# can-stm32g4.net
KiCad netlist of a schematic drawn in Altium Designer
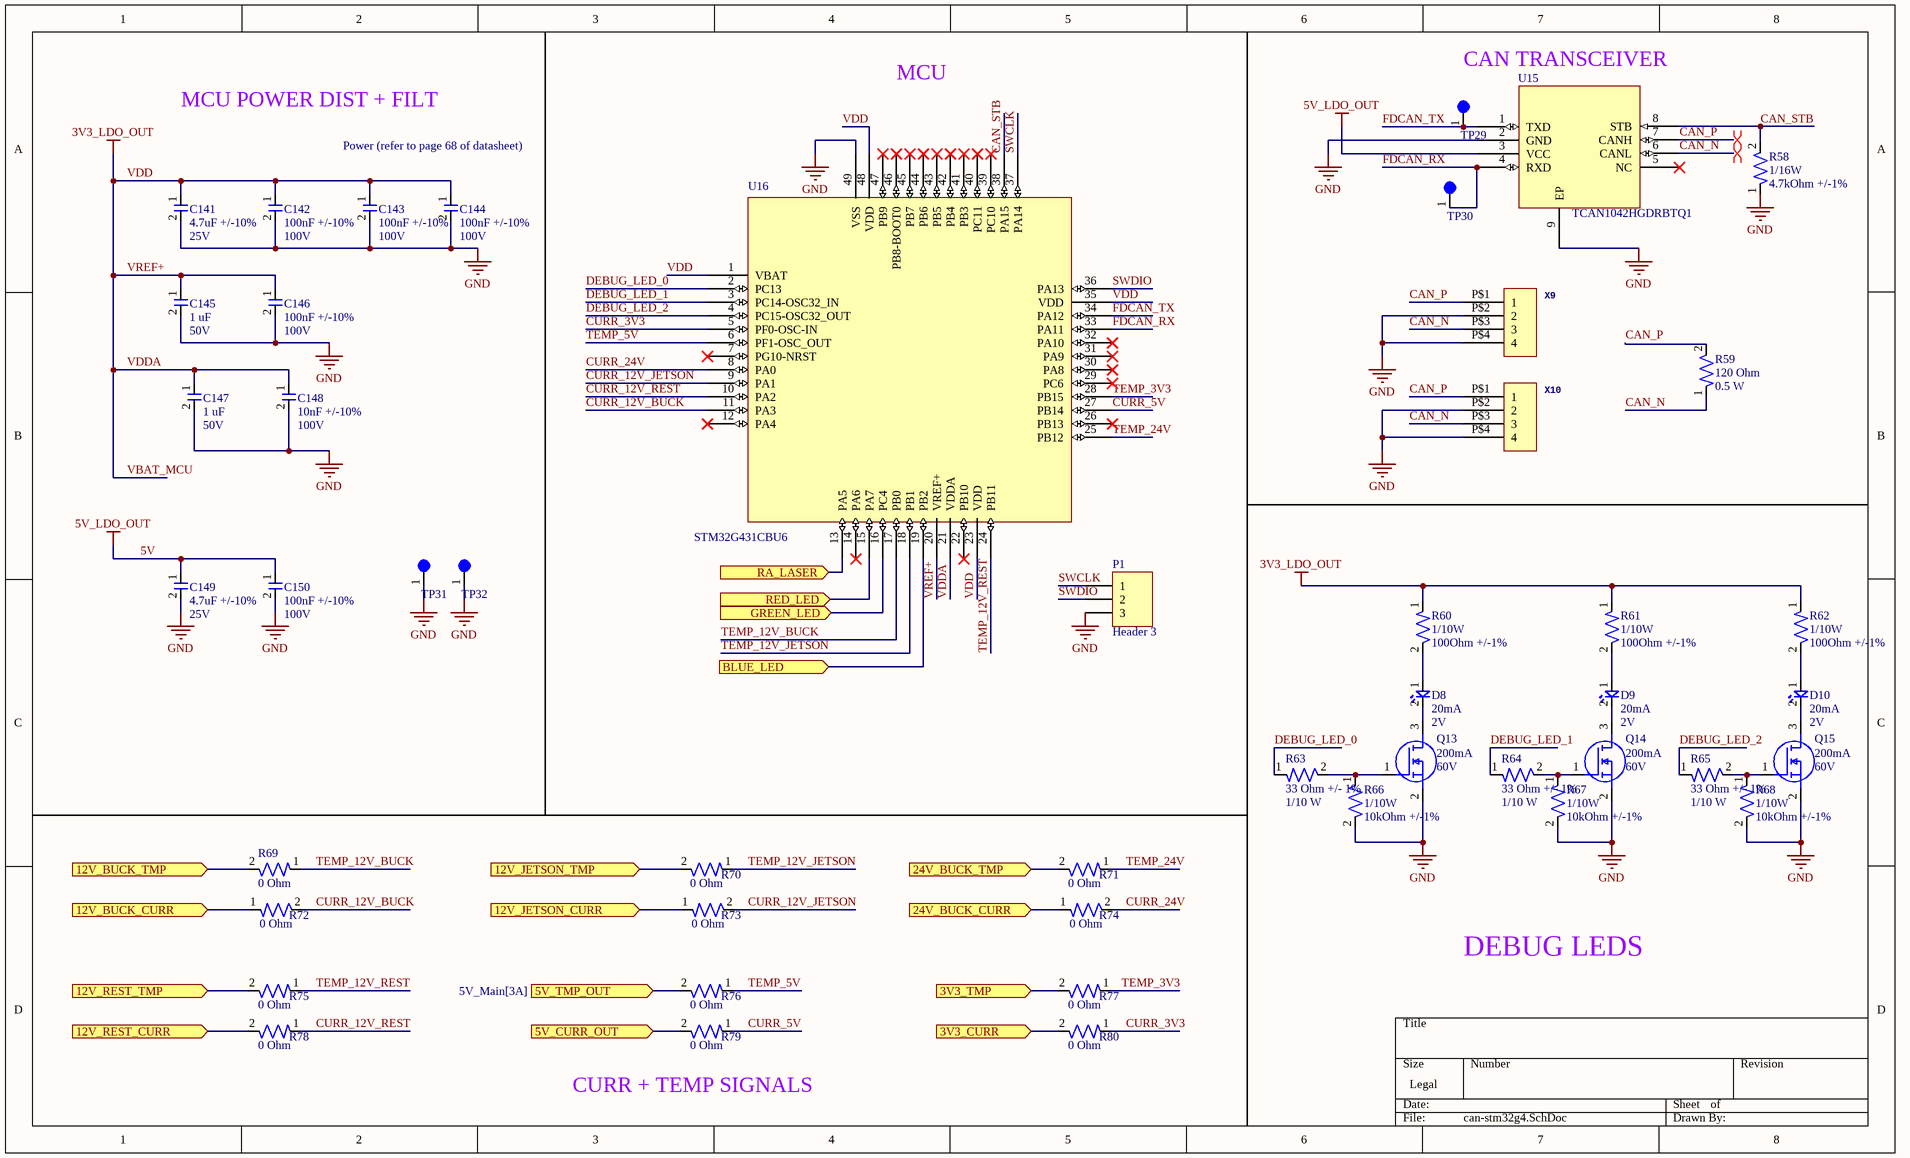
[diagram p0: can-stm32g4.SchDoc]

(export (version "E")
  (design (tool "Eeschema 10.0.6"))
  (components
    (comp (ref "C141")
      (value "TMK107BBJ475KA-T")
      (footprint "CAP-0603")
      (description "4.7 µF ±10% 25V Ceramic Capacitor X5R 0603 (1608 Metric)")
      (fields
        (field (name "MANUFACTURER") "Taiyo Yuden")
        (field (name "CAPACITANCE") "4.7uF +/-10%")
        (field (name "VOLTAGE RATING") "25V")
      )
      (libsource (lib "MasterLib") (part "CAP-4.7U-0001"))
    )
    (comp (ref "C142")
      (value "CC0603KRX7R0BB104")
      (footprint "CAP-0603")
      (description "CAP CER 0.1UF 100V X7R 0603")
      (fields
        (field (name "MANUFACTURER") "YAGEO")
        (field (name "CAPACITANCE") "100nF +/-10%")
        (field (name "VOLTAGE RATING") "100V")
      )
      (libsource (lib "MasterLib") (part "CAP-100N-0001"))
    )
    (comp (ref "C143")
      (value "CC0603KRX7R0BB104")
      (footprint "CAP-0603")
      (description "CAP CER 0.1UF 100V X7R 0603")
      (fields
        (field (name "MANUFACTURER") "YAGEO")
        (field (name "CAPACITANCE") "100nF +/-10%")
        (field (name "VOLTAGE RATING") "100V")
      )
      (libsource (lib "MasterLib") (part "CAP-100N-0001"))
    )
    (comp (ref "C144")
      (value "CC0603KRX7R0BB104")
      (footprint "CAP-0603")
      (description "CAP CER 0.1UF 100V X7R 0603")
      (fields
        (field (name "MANUFACTURER") "YAGEO")
        (field (name "CAPACITANCE") "100nF +/-10%")
        (field (name "VOLTAGE RATING") "100V")
      )
      (libsource (lib "MasterLib") (part "CAP-100N-0001"))
    )
    (comp (ref "C145")
      (value "UMK107AB7105KA-T")
      (footprint "CAP-0603")
      (description "1 µF ±10% 50V Ceramic Capacitor X7R 0603 (1608 Metric)")
      (fields (field (name "CAPACITANCE") "1 uF") (field (name "VOLTAGE") "50V"))
      (libsource (lib "MasterLib") (part "CAP-1U-0002"))
    )
    (comp (ref "C146")
      (value "CC0603KRX7R0BB104")
      (footprint "CAP-0603")
      (description "CAP CER 0.1UF 100V X7R 0603")
      (fields
        (field (name "MANUFACTURER") "YAGEO")
        (field (name "CAPACITANCE") "100nF +/-10%")
        (field (name "VOLTAGE RATING") "100V")
      )
      (libsource (lib "MasterLib") (part "CAP-100N-0001"))
    )
    (comp (ref "C147")
      (value "UMK107AB7105KA-T")
      (footprint "CAP-0603")
      (description "1 µF ±10% 50V Ceramic Capacitor X7R 0603 (1608 Metric)")
      (fields (field (name "CAPACITANCE") "1 uF") (field (name "VOLTAGE") "50V"))
      (libsource (lib "MasterLib") (part "CAP-1U-0002"))
    )
    (comp (ref "C148")
      (value "CC0402KRX7R0BB103")
      (footprint "CAP-0402")
      (description "10000 pF ±10% 100V Ceramic Capacitor X7R 0402 (1005 Metric)")
      (fields
        (field (name "MANUFACTURER") "YAGEO")
        (field (name "CAPACITANCE") "10nF +/-10%")
        (field (name "VOLTAGE RATING") "100V")
      )
      (libsource (lib "MasterLib") (part "CAP-10N-0001"))
    )
    (comp (ref "C149")
      (value "TMK107BBJ475KA-T")
      (footprint "CAP-0603")
      (description "4.7 µF ±10% 25V Ceramic Capacitor X5R 0603 (1608 Metric)")
      (fields
        (field (name "MANUFACTURER") "Taiyo Yuden")
        (field (name "CAPACITANCE") "4.7uF +/-10%")
        (field (name "VOLTAGE RATING") "25V")
      )
      (libsource (lib "MasterLib") (part "CAP-4.7U-0001"))
    )
    (comp (ref "C150")
      (value "CC0603KRX7R0BB104")
      (footprint "CAP-0603")
      (description "CAP CER 0.1UF 100V X7R 0603")
      (fields
        (field (name "MANUFACTURER") "YAGEO")
        (field (name "CAPACITANCE") "100nF +/-10%")
        (field (name "VOLTAGE RATING") "100V")
      )
      (libsource (lib "MasterLib") (part "CAP-100N-0001"))
    )
    (comp (ref "D8")
      (value "150060AS75000")
      (footprint "LED-0603")
      (description "CAP CER 0.1UF 100V X7R 0603")
      (fields
        (field (name "MANUFACTURER") "Wurth Electronik")
        (field (name "CURRENT RATING") "20mA")
        (field (name "VF") "2V")
      )
      (libsource (lib "MasterLib") (part "LED_Amber_0001"))
    )
    (comp (ref "D9")
      (value "150060AS75000")
      (footprint "LED-0603")
      (description "CAP CER 0.1UF 100V X7R 0603")
      (fields
        (field (name "MANUFACTURER") "Wurth Electronik")
        (field (name "CURRENT RATING") "20mA")
        (field (name "VF") "2V")
      )
      (libsource (lib "MasterLib") (part "LED_Amber_0001"))
    )
    (comp (ref "D10")
      (value "150060AS75000")
      (footprint "LED-0603")
      (description "CAP CER 0.1UF 100V X7R 0603")
      (fields
        (field (name "MANUFACTURER") "Wurth Electronik")
        (field (name "CURRENT RATING") "20mA")
        (field (name "VF") "2V")
      )
      (libsource (lib "MasterLib") (part "LED_Amber_0001"))
    )
    (comp (ref "P1")
      (value "Header 3")
      (footprint "HDR1X3")
      (description "Header, 3-Pin")
      (fields (field (name "PUBLISHER") "Altium Limited"))
      (libsource (lib "Miscellaneous Connectors") (part "Header 3"))
    )
    (comp (ref "Q13")
      (value "T2N7002AK,LM")
      (footprint "NMOS-SOT23-3")
      (description "MOSFET N-CH 60V 200MA SOT23")
      (fields
        (field (name "MANUFACTURER") "Toshiba")
        (field (name "ID-CONTINUOUS") "200mA")
        (field (name "VDS-MAX") "60V")
      )
      (libsource (lib "MasterLib") (part "NMOS-200MA-0001"))
    )
    (comp (ref "Q14")
      (value "T2N7002AK,LM")
      (footprint "NMOS-SOT23-3")
      (description "MOSFET N-CH 60V 200MA SOT23")
      (fields
        (field (name "MANUFACTURER") "Toshiba")
        (field (name "ID-CONTINUOUS") "200mA")
        (field (name "VDS-MAX") "60V")
      )
      (libsource (lib "MasterLib") (part "NMOS-200MA-0001"))
    )
    (comp (ref "Q15")
      (value "T2N7002AK,LM")
      (footprint "NMOS-SOT23-3")
      (description "MOSFET N-CH 60V 200MA SOT23")
      (fields
        (field (name "MANUFACTURER") "Toshiba")
        (field (name "ID-CONTINUOUS") "200mA")
        (field (name "VDS-MAX") "60V")
      )
      (libsource (lib "MasterLib") (part "NMOS-200MA-0001"))
    )
    (comp (ref "R58")
      (value "RC0402FR-074K7P")
      (footprint "RES-0402")
      (description "RES SMD 4.7K OHM 1% 1/16W 0402")
      (fields
        (field (name "MANUFACTURER") "YAGEO")
        (field (name "POWER RATING") "1/16W")
        (field (name "RESISTANCE") "4.7kOhm +/-1%")
      )
      (libsource (lib "MasterLib") (part "RES-4.7K-0001"))
    )
    (comp (ref "R59")
      (value "CRGH1206F120R")
      (footprint "RES-1206")
      (description "120 Ohms ±1% 0.5W, 1/2W Chip Resistor 1206 (3216 Metric) Thick Film")
      (fields
        (field (name "TOLERANCE") "1%")
        (field (name "RESISTANCE") "120 Ohm")
        (field (name "POWER") "0.5 W")
      )
      (libsource (lib "MasterLib") (part "RES-120-0002"))
    )
    (comp (ref "R60")
      (value "AC0603FR-10100RL")
      (footprint "RES-0603")
      (description "100 Ohms ±1% 0.1W, 1/10W Chip Resistor 0603 (1608 Metric) Automotive AEC-Q200 Thick Film")
      (fields
        (field (name "MANUFACTURER") "YAGEO")
        (field (name "POWER RATING") "1/10W")
        (field (name "RESISTANCE") "100Ohm +/-1%")
      )
      (libsource (lib "MasterLib") (part "RES-100-0002"))
    )
    (comp (ref "R61")
      (value "AC0603FR-10100RL")
      (footprint "RES-0603")
      (description "100 Ohms ±1% 0.1W, 1/10W Chip Resistor 0603 (1608 Metric) Automotive AEC-Q200 Thick Film")
      (fields
        (field (name "MANUFACTURER") "YAGEO")
        (field (name "POWER RATING") "1/10W")
        (field (name "RESISTANCE") "100Ohm +/-1%")
      )
      (libsource (lib "MasterLib") (part "RES-100-0002"))
    )
    (comp (ref "R62")
      (value "AC0603FR-10100RL")
      (footprint "RES-0603")
      (description "100 Ohms ±1% 0.1W, 1/10W Chip Resistor 0603 (1608 Metric) Automotive AEC-Q200 Thick Film")
      (fields
        (field (name "MANUFACTURER") "YAGEO")
        (field (name "POWER RATING") "1/10W")
        (field (name "RESISTANCE") "100Ohm +/-1%")
      )
      (libsource (lib "MasterLib") (part "RES-100-0002"))
    )
    (comp (ref "R63")
      (value "ERJ2RKF33R0X")
      (footprint "RES-0402")
      (description "100mW Thick Film Resistors ±100ppm/℃ ±1% -55℃~+155℃ 33Ω 0402  Chip Resistor - Surface Mount ROHS")
      (fields
        (field (name "RESISTANCE") "33 Ohm +/- 1%")
        (field (name "POWER") "1/10 W")
        (field (name "JLC PART NUMBER") "C278594")
      )
      (libsource (lib "MasterLib") (part "RES-33-0003-JLC"))
    )
    (comp (ref "R64")
      (value "ERJ2RKF33R0X")
      (footprint "RES-0402")
      (description "100mW Thick Film Resistors ±100ppm/℃ ±1% -55℃~+155℃ 33Ω 0402  Chip Resistor - Surface Mount ROHS")
      (fields
        (field (name "RESISTANCE") "33 Ohm +/- 1%")
        (field (name "POWER") "1/10 W")
        (field (name "JLC PART NUMBER") "C278594")
      )
      (libsource (lib "MasterLib") (part "RES-33-0003-JLC"))
    )
    (comp (ref "R65")
      (value "ERJ2RKF33R0X")
      (footprint "RES-0402")
      (description "100mW Thick Film Resistors ±100ppm/℃ ±1% -55℃~+155℃ 33Ω 0402  Chip Resistor - Surface Mount ROHS")
      (fields
        (field (name "RESISTANCE") "33 Ohm +/- 1%")
        (field (name "POWER") "1/10 W")
        (field (name "JLC PART NUMBER") "C278594")
      )
      (libsource (lib "MasterLib") (part "RES-33-0003-JLC"))
    )
    (comp (ref "R66")
      (value "RC0603FR-0710KP")
      (footprint "RES-0603")
      (description "RES SMD 10K OHM 1% 1/10W 0603")
      (fields
        (field (name "MANUFACTURER") "YAGEO")
        (field (name "POWER RATING") "1/10W")
        (field (name "RESISTANCE") "10kOhm +/-1%")
      )
      (libsource (lib "MasterLib") (part "RES-10K-0002"))
    )
    (comp (ref "R67")
      (value "RC0603FR-0710KP")
      (footprint "RES-0603")
      (description "RES SMD 10K OHM 1% 1/10W 0603")
      (fields
        (field (name "MANUFACTURER") "YAGEO")
        (field (name "POWER RATING") "1/10W")
        (field (name "RESISTANCE") "10kOhm +/-1%")
      )
      (libsource (lib "MasterLib") (part "RES-10K-0002"))
    )
    (comp (ref "R68")
      (value "RC0603FR-0710KP")
      (footprint "RES-0603")
      (description "RES SMD 10K OHM 1% 1/10W 0603")
      (fields
        (field (name "MANUFACTURER") "YAGEO")
        (field (name "POWER RATING") "1/10W")
        (field (name "RESISTANCE") "10kOhm +/-1%")
      )
      (libsource (lib "MasterLib") (part "RES-10K-0002"))
    )
    (comp (ref "R69")
      (value "RMCF0603ZT0R00")
      (footprint "RES-0603")
      (description "0 Ohms Jumper 0.1W, 1/10W Chip Resistor 0603 (1608 Metric) Automotive AEC-Q200 Thick Film")
      (fields (field (name "RESISTANCE") "0 Ohm"))
      (libsource (lib "MasterLib") (part "RES-0-0001"))
    )
    (comp (ref "R70")
      (value "RMCF0603ZT0R00")
      (footprint "RES-0603")
      (description "0 Ohms Jumper 0.1W, 1/10W Chip Resistor 0603 (1608 Metric) Automotive AEC-Q200 Thick Film")
      (fields (field (name "RESISTANCE") "0 Ohm"))
      (libsource (lib "MasterLib") (part "RES-0-0001"))
    )
    (comp (ref "R71")
      (value "RMCF0603ZT0R00")
      (footprint "RES-0603")
      (description "0 Ohms Jumper 0.1W, 1/10W Chip Resistor 0603 (1608 Metric) Automotive AEC-Q200 Thick Film")
      (fields (field (name "RESISTANCE") "0 Ohm"))
      (libsource (lib "MasterLib") (part "RES-0-0001"))
    )
    (comp (ref "R72")
      (value "RMCF0603ZT0R00")
      (footprint "RES-0603")
      (description "0 Ohms Jumper 0.1W, 1/10W Chip Resistor 0603 (1608 Metric) Automotive AEC-Q200 Thick Film")
      (fields (field (name "RESISTANCE") "0 Ohm"))
      (libsource (lib "MasterLib") (part "RES-0-0001"))
    )
    (comp (ref "R73")
      (value "RMCF0603ZT0R00")
      (footprint "RES-0603")
      (description "0 Ohms Jumper 0.1W, 1/10W Chip Resistor 0603 (1608 Metric) Automotive AEC-Q200 Thick Film")
      (fields (field (name "RESISTANCE") "0 Ohm"))
      (libsource (lib "MasterLib") (part "RES-0-0001"))
    )
    (comp (ref "R74")
      (value "RMCF0603ZT0R00")
      (footprint "RES-0603")
      (description "0 Ohms Jumper 0.1W, 1/10W Chip Resistor 0603 (1608 Metric) Automotive AEC-Q200 Thick Film")
      (fields (field (name "RESISTANCE") "0 Ohm"))
      (libsource (lib "MasterLib") (part "RES-0-0001"))
    )
    (comp (ref "R75")
      (value "RMCF0603ZT0R00")
      (footprint "RES-0603")
      (description "0 Ohms Jumper 0.1W, 1/10W Chip Resistor 0603 (1608 Metric) Automotive AEC-Q200 Thick Film")
      (fields (field (name "RESISTANCE") "0 Ohm"))
      (libsource (lib "MasterLib") (part "RES-0-0001"))
    )
    (comp (ref "R76")
      (value "RMCF0603ZT0R00")
      (footprint "RES-0603")
      (description "0 Ohms Jumper 0.1W, 1/10W Chip Resistor 0603 (1608 Metric) Automotive AEC-Q200 Thick Film")
      (fields (field (name "RESISTANCE") "0 Ohm"))
      (libsource (lib "MasterLib") (part "RES-0-0001"))
    )
    (comp (ref "R77")
      (value "RMCF0603ZT0R00")
      (footprint "RES-0603")
      (description "0 Ohms Jumper 0.1W, 1/10W Chip Resistor 0603 (1608 Metric) Automotive AEC-Q200 Thick Film")
      (fields (field (name "RESISTANCE") "0 Ohm"))
      (libsource (lib "MasterLib") (part "RES-0-0001"))
    )
    (comp (ref "R78")
      (value "RMCF0603ZT0R00")
      (footprint "RES-0603")
      (description "0 Ohms Jumper 0.1W, 1/10W Chip Resistor 0603 (1608 Metric) Automotive AEC-Q200 Thick Film")
      (fields (field (name "RESISTANCE") "0 Ohm"))
      (libsource (lib "MasterLib") (part "RES-0-0001"))
    )
    (comp (ref "R79")
      (value "RMCF0603ZT0R00")
      (footprint "RES-0603")
      (description "0 Ohms Jumper 0.1W, 1/10W Chip Resistor 0603 (1608 Metric) Automotive AEC-Q200 Thick Film")
      (fields (field (name "RESISTANCE") "0 Ohm"))
      (libsource (lib "MasterLib") (part "RES-0-0001"))
    )
    (comp (ref "R80")
      (value "RMCF0603ZT0R00")
      (footprint "RES-0603")
      (description "0 Ohms Jumper 0.1W, 1/10W Chip Resistor 0603 (1608 Metric) Automotive AEC-Q200 Thick Film")
      (fields (field (name "RESISTANCE") "0 Ohm"))
      (libsource (lib "MasterLib") (part "RES-0-0001"))
    )
    (comp (ref "TP29")
      (value "5003")
      (footprint "TEST-POINT-0001")
      (description "Oranange PC Test Point, Miniature Phoisphor Bronze Silver Plating Through Hole Mounting Type")
      (libsource (lib "MasterLib") (part "TEST-POINT-0001"))
    )
    (comp (ref "TP30")
      (value "5003")
      (footprint "TEST-POINT-0001")
      (description "Oranange PC Test Point, Miniature Phoisphor Bronze Silver Plating Through Hole Mounting Type")
      (libsource (lib "MasterLib") (part "TEST-POINT-0001"))
    )
    (comp (ref "TP31")
      (value "5003")
      (footprint "TEST-POINT-0001")
      (description "Oranange PC Test Point, Miniature Phoisphor Bronze Silver Plating Through Hole Mounting Type")
      (libsource (lib "MasterLib") (part "TEST-POINT-0001"))
    )
    (comp (ref "TP32")
      (value "5003")
      (footprint "TEST-POINT-0001")
      (description "Oranange PC Test Point, Miniature Phoisphor Bronze Silver Plating Through Hole Mounting Type")
      (libsource (lib "MasterLib") (part "TEST-POINT-0001"))
    )
    (comp (ref "U15")
      (value "TCAN1042HGDRBTQ1")
      (footprint "IC-8-VSON")
      (description "1/1 Transceiver CANbus 8-VSON (3x3)")
      (fields (field (name "MANUFACTURER") "Texas Instrument"))
      (libsource (lib "MasterLib") (part "IC-CAN-TRANSCEIVER-0002"))
    )
    (comp (ref "U16")
      (value "STM32G431CBU6")
      (footprint "MCU-UFQFPN48")
      (libsource (lib "MasterLib") (part "IC-STM32G431CBU6"))
    )
    (comp (ref "X9")
      (value "Molex 43045-0412")
      (footprint "43045-0412")
      (libsource (lib "Molex Microfit") (part "Micro-Fit Molex 4 Pin 2 Row Vertical"))
    )
    (comp (ref "X10")
      (value "Molex 43045-0412")
      (footprint "43045-0412")
      (libsource (lib "Molex Microfit") (part "Micro-Fit Molex 4 Pin 2 Row Vertical"))
    )
  )
  (nets
    (net (code "1") (name "/3V3_CURR") (class "Default")
      (node (ref "R80") (pin "2") (pinfunction "2_2") (pintype "passive"))
    )
    (net (code "2") (name "/3V3_TMP") (class "Default")
      (node (ref "R77") (pin "2") (pinfunction "2_2") (pintype "passive"))
    )
    (net (code "3") (name "/5V_CURR_OUT") (class "Default")
      (node (ref "R79") (pin "2") (pinfunction "2_2") (pintype "passive"))
    )
    (net (code "4") (name "/5V_TMP_OUT") (class "Default")
      (node (ref "R76") (pin "2") (pinfunction "2_2") (pintype "passive"))
    )
    (net (code "5") (name "/12V_BUCK_CURR") (class "Default")
      (node (ref "R72") (pin "1") (pinfunction "1_1") (pintype "passive"))
    )
    (net (code "6") (name "/12V_BUCK_TMP") (class "Default")
      (node (ref "R69") (pin "2") (pinfunction "2_2") (pintype "passive"))
    )
    (net (code "7") (name "/12V_JETSON_CURR") (class "Default")
      (node (ref "R73") (pin "1") (pinfunction "1_1") (pintype "passive"))
    )
    (net (code "8") (name "/12V_JETSON_TMP") (class "Default")
      (node (ref "R70") (pin "2") (pinfunction "2_2") (pintype "passive"))
    )
    (net (code "9") (name "/12V_REST_CURR") (class "Default")
      (node (ref "R78") (pin "2") (pinfunction "2_2") (pintype "passive"))
    )
    (net (code "10") (name "/12V_REST_TMP") (class "Default")
      (node (ref "R75") (pin "2") (pinfunction "2_2") (pintype "passive"))
    )
    (net (code "11") (name "/24V_BUCK_CURR") (class "Default")
      (node (ref "R74") (pin "1") (pinfunction "1_1") (pintype "passive"))
    )
    (net (code "12") (name "/24V_BUCK_TMP") (class "Default")
      (node (ref "R71") (pin "2") (pinfunction "2_2") (pintype "passive"))
    )
    (net (code "14") (name "/BLUE_LED") (class "Default")
      (node (ref "U16") (pin "19") (pinfunction "PB2_19") (pintype "bidirectional"))
    )
    (net (code "15") (name "/CAN_N") (class "Default")
      (node (ref "R59") (pin "1") (pinfunction "1_1") (pintype "passive"))
      (node (ref "U15") (pin "6") (pinfunction "CANL_6") (pintype "bidirectional"))
      (node (ref "X10") (pin "P$3") (pinfunction "3_P$3") (pintype "passive"))
      (node (ref "X9") (pin "P$3") (pinfunction "3_P$3") (pintype "passive"))
    )
    (net (code "16") (name "/CAN_P") (class "Default")
      (node (ref "R59") (pin "2") (pinfunction "2_2") (pintype "passive"))
      (node (ref "U15") (pin "7") (pinfunction "CANH_7") (pintype "bidirectional"))
      (node (ref "X10") (pin "P$1") (pinfunction "1_P$1") (pintype "passive"))
      (node (ref "X9") (pin "P$1") (pinfunction "1_P$1") (pintype "passive"))
    )
    (net (code "17") (name "/CAN_STB") (class "Default")
      (node (ref "R58") (pin "2") (pinfunction "2_2") (pintype "passive"))
      (node (ref "U15") (pin "8") (pinfunction "STB_8") (pintype "input"))
      (node (ref "U16") (pin "38") (pinfunction "PA15_38") (pintype "bidirectional"))
    )
    (net (code "18") (name "/CURR_3V3") (class "Default")
      (node (ref "R80") (pin "1") (pinfunction "1_1") (pintype "passive"))
      (node (ref "U16") (pin "5") (pinfunction "PF0-OSC-IN_5") (pintype "bidirectional"))
    )
    (net (code "19") (name "/CURR_5V") (class "Default")
      (node (ref "R79") (pin "1") (pinfunction "1_1") (pintype "passive"))
      (node (ref "U16") (pin "27") (pinfunction "PB14_27") (pintype "bidirectional"))
    )
    (net (code "20") (name "/CURR_12V_BUCK") (class "Default")
      (node (ref "R72") (pin "2") (pinfunction "2_2") (pintype "passive"))
      (node (ref "U16") (pin "11") (pinfunction "PA3_11") (pintype "bidirectional"))
    )
    (net (code "21") (name "/CURR_12V_JETSON") (class "Default")
      (node (ref "R73") (pin "2") (pinfunction "2_2") (pintype "passive"))
      (node (ref "U16") (pin "9") (pinfunction "PA1_9") (pintype "bidirectional"))
    )
    (net (code "22") (name "/CURR_12V_REST") (class "Default")
      (node (ref "R78") (pin "1") (pinfunction "1_1") (pintype "passive"))
      (node (ref "U16") (pin "10") (pinfunction "PA2_10") (pintype "bidirectional"))
    )
    (net (code "23") (name "/CURR_24V") (class "Default")
      (node (ref "R74") (pin "2") (pinfunction "2_2") (pintype "passive"))
      (node (ref "U16") (pin "8") (pinfunction "PA0_8") (pintype "bidirectional"))
    )
    (net (code "24") (name "/DEBUG_LED_0") (class "Default")
      (node (ref "R63") (pin "1") (pinfunction "1_1") (pintype "passive"))
      (node (ref "U16") (pin "2") (pinfunction "PC13_2") (pintype "bidirectional"))
    )
    (net (code "25") (name "/DEBUG_LED_1") (class "Default")
      (node (ref "R64") (pin "1") (pinfunction "1_1") (pintype "passive"))
      (node (ref "U16") (pin "3") (pinfunction "PC14-OSC32_IN_3") (pintype "bidirectional"))
    )
    (net (code "26") (name "/DEBUG_LED_2") (class "Default")
      (node (ref "R65") (pin "1") (pinfunction "1_1") (pintype "passive"))
      (node (ref "U16") (pin "4") (pinfunction "PC15-OSC32_OUT_4") (pintype "bidirectional"))
    )
    (net (code "27") (name "/FDCAN_RX") (class "Default")
      (node (ref "TP30") (pin "1") (pinfunction "0_1") (pintype "passive"))
      (node (ref "U15") (pin "4") (pinfunction "RXD_4") (pintype "bidirectional"))
      (node (ref "U16") (pin "33") (pinfunction "PA11_33") (pintype "bidirectional"))
    )
    (net (code "28") (name "/FDCAN_TX") (class "Default")
      (node (ref "TP29") (pin "1") (pinfunction "0_1") (pintype "passive"))
      (node (ref "U15") (pin "1") (pinfunction "TXD_1") (pintype "bidirectional"))
      (node (ref "U16") (pin "34") (pinfunction "PA12_34") (pintype "bidirectional"))
    )
    (net (code "29") (name "/GREEN_LED") (class "Default")
      (node (ref "U16") (pin "16") (pinfunction "PC4_16") (pintype "bidirectional"))
    )
    (net (code "30") (name "/RA_LASER") (class "Default")
      (node (ref "U16") (pin "13") (pinfunction "PA5_13") (pintype "bidirectional"))
    )
    (net (code "31") (name "/RED_LED") (class "Default")
      (node (ref "U16") (pin "15") (pinfunction "PA7_15") (pintype "bidirectional"))
    )
    (net (code "32") (name "/SWCLK") (class "Default")
      (node (ref "P1") (pin "1") (pinfunction "1_1") (pintype "passive"))
      (node (ref "U16") (pin "37") (pinfunction "PA14_37") (pintype "bidirectional"))
    )
    (net (code "33") (name "/SWDIO") (class "Default")
      (node (ref "P1") (pin "2") (pinfunction "2_2") (pintype "passive"))
      (node (ref "U16") (pin "36") (pinfunction "PA13_36") (pintype "bidirectional"))
    )
    (net (code "34") (name "/TEMP_3V3") (class "Default")
      (node (ref "R77") (pin "1") (pinfunction "1_1") (pintype "passive"))
      (node (ref "U16") (pin "28") (pinfunction "PB15_28") (pintype "bidirectional"))
    )
    (net (code "35") (name "/TEMP_5V") (class "Default")
      (node (ref "R76") (pin "1") (pinfunction "1_1") (pintype "passive"))
      (node (ref "U16") (pin "6") (pinfunction "PF1-OSC_OUT_6") (pintype "bidirectional"))
    )
    (net (code "36") (name "/TEMP_12V_BUCK") (class "Default")
      (node (ref "R69") (pin "1") (pinfunction "1_1") (pintype "passive"))
      (node (ref "U16") (pin "17") (pinfunction "PB0_17") (pintype "bidirectional"))
    )
    (net (code "37") (name "/TEMP_12V_JETSON") (class "Default")
      (node (ref "R70") (pin "1") (pinfunction "1_1") (pintype "passive"))
      (node (ref "U16") (pin "18") (pinfunction "PB1_18") (pintype "bidirectional"))
    )
    (net (code "38") (name "/TEMP_12V_REST") (class "Default")
      (node (ref "R75") (pin "1") (pinfunction "1_1") (pintype "passive"))
      (node (ref "U16") (pin "24") (pinfunction "PB11_24") (pintype "bidirectional"))
    )
    (net (code "39") (name "/TEMP_24V") (class "Default")
      (node (ref "R71") (pin "1") (pinfunction "1_1") (pintype "passive"))
      (node (ref "U16") (pin "25") (pinfunction "PB12_25") (pintype "bidirectional"))
    )
    (net (code "40") (name "3V3_LDO_OUT") (class "Default")
      (node (ref "C141") (pin "1") (pinfunction "1_1") (pintype "passive"))
      (node (ref "C142") (pin "1") (pinfunction "1_1") (pintype "passive"))
      (node (ref "C143") (pin "1") (pinfunction "1_1") (pintype "passive"))
      (node (ref "C144") (pin "1") (pinfunction "1_1") (pintype "passive"))
      (node (ref "C145") (pin "1") (pinfunction "1_1") (pintype "passive"))
      (node (ref "C146") (pin "1") (pinfunction "1_1") (pintype "passive"))
      (node (ref "C147") (pin "1") (pinfunction "1_1") (pintype "passive"))
      (node (ref "C148") (pin "1") (pinfunction "1_1") (pintype "passive"))
      (node (ref "R60") (pin "1") (pinfunction "1_1") (pintype "passive"))
      (node (ref "R61") (pin "1") (pinfunction "1_1") (pintype "passive"))
      (node (ref "R62") (pin "1") (pinfunction "1_1") (pintype "passive"))
      (node (ref "U16") (pin "1") (pinfunction "VBAT_1") (pintype "power_in"))
      (node (ref "U16") (pin "20") (pinfunction "VREF+_20") (pintype "power_in"))
      (node (ref "U16") (pin "21") (pinfunction "VDDA_21") (pintype "power_in"))
      (node (ref "U16") (pin "23") (pinfunction "VDD_23") (pintype "power_in"))
      (node (ref "U16") (pin "35") (pinfunction "VDD_35") (pintype "power_in"))
      (node (ref "U16") (pin "48") (pinfunction "VDD_48") (pintype "power_in"))
    )
    (net (code "41") (name "5V_LDO_OUT") (class "Default")
      (node (ref "C149") (pin "1") (pinfunction "1_1") (pintype "passive"))
      (node (ref "C150") (pin "1") (pinfunction "1_1") (pintype "passive"))
      (node (ref "U15") (pin "3") (pinfunction "VCC_3") (pintype "power_in"))
    )
    (net (code "42") (name "GND") (class "Default")
      (node (ref "C141") (pin "2") (pinfunction "2_2") (pintype "passive"))
      (node (ref "C142") (pin "2") (pinfunction "2_2") (pintype "passive"))
      (node (ref "C143") (pin "2") (pinfunction "2_2") (pintype "passive"))
      (node (ref "C144") (pin "2") (pinfunction "2_2") (pintype "passive"))
      (node (ref "C145") (pin "2") (pinfunction "2_2") (pintype "passive"))
      (node (ref "C146") (pin "2") (pinfunction "2_2") (pintype "passive"))
      (node (ref "C147") (pin "2") (pinfunction "2_2") (pintype "passive"))
      (node (ref "C148") (pin "2") (pinfunction "2_2") (pintype "passive"))
      (node (ref "C149") (pin "2") (pinfunction "2_2") (pintype "passive"))
      (node (ref "C150") (pin "2") (pinfunction "2_2") (pintype "passive"))
      (node (ref "P1") (pin "3") (pinfunction "3_3") (pintype "passive"))
      (node (ref "Q13") (pin "2") (pinfunction "S_2") (pintype "passive"))
      (node (ref "Q14") (pin "2") (pinfunction "S_2") (pintype "passive"))
      (node (ref "Q15") (pin "2") (pinfunction "S_2") (pintype "passive"))
      (node (ref "R58") (pin "1") (pinfunction "1_1") (pintype "passive"))
      (node (ref "R66") (pin "2") (pinfunction "2_2") (pintype "passive"))
      (node (ref "R67") (pin "2") (pinfunction "2_2") (pintype "passive"))
      (node (ref "R68") (pin "2") (pinfunction "2_2") (pintype "passive"))
      (node (ref "TP31") (pin "1") (pinfunction "0_1") (pintype "passive"))
      (node (ref "TP32") (pin "1") (pinfunction "0_1") (pintype "passive"))
      (node (ref "U15") (pin "2") (pinfunction "GND_2") (pintype "power_in"))
      (node (ref "U15") (pin "9") (pinfunction "EP_9") (pintype "power_in"))
      (node (ref "U16") (pin "49") (pinfunction "VSS_49") (pintype "power_in"))
      (node (ref "X10") (pin "P$2") (pinfunction "2_P$2") (pintype "passive"))
      (node (ref "X10") (pin "P$4") (pinfunction "4_P$4") (pintype "passive"))
      (node (ref "X9") (pin "P$2") (pinfunction "2_P$2") (pintype "passive"))
      (node (ref "X9") (pin "P$4") (pinfunction "4_P$4") (pintype "passive"))
    )
    (net (code "43") (name "Net-(D8-Pad1)") (class "Default")
      (node (ref "D8") (pin "1") (pinfunction "1_1") (pintype "passive"))
      (node (ref "R60") (pin "2") (pinfunction "2_2") (pintype "passive"))
    )
    (net (code "44") (name "Net-(D9-Pad1)") (class "Default")
      (node (ref "D9") (pin "1") (pinfunction "1_1") (pintype "passive"))
      (node (ref "R61") (pin "2") (pinfunction "2_2") (pintype "passive"))
    )
    (net (code "45") (name "Net-(D10-Pad1)") (class "Default")
      (node (ref "D10") (pin "1") (pinfunction "1_1") (pintype "passive"))
      (node (ref "R62") (pin "2") (pinfunction "2_2") (pintype "passive"))
    )
    (net (code "46") (name "Net-(Q13-D)") (class "Default")
      (node (ref "D8") (pin "2") (pinfunction "2_2") (pintype "passive"))
      (node (ref "Q13") (pin "3") (pinfunction "D_3") (pintype "passive"))
    )
    (net (code "47") (name "Net-(Q13-G)") (class "Default")
      (node (ref "Q13") (pin "1") (pinfunction "G_1") (pintype "passive"))
      (node (ref "R63") (pin "2") (pinfunction "2_2") (pintype "passive"))
      (node (ref "R66") (pin "1") (pinfunction "1_1") (pintype "passive"))
    )
    (net (code "48") (name "Net-(Q14-D)") (class "Default")
      (node (ref "D9") (pin "2") (pinfunction "2_2") (pintype "passive"))
      (node (ref "Q14") (pin "3") (pinfunction "D_3") (pintype "passive"))
    )
    (net (code "49") (name "Net-(Q14-G)") (class "Default")
      (node (ref "Q14") (pin "1") (pinfunction "G_1") (pintype "passive"))
      (node (ref "R64") (pin "2") (pinfunction "2_2") (pintype "passive"))
      (node (ref "R67") (pin "1") (pinfunction "1_1") (pintype "passive"))
    )
    (net (code "50") (name "Net-(Q15-D)") (class "Default")
      (node (ref "D10") (pin "2") (pinfunction "2_2") (pintype "passive"))
      (node (ref "Q15") (pin "3") (pinfunction "D_3") (pintype "passive"))
    )
    (net (code "51") (name "Net-(Q15-G)") (class "Default")
      (node (ref "Q15") (pin "1") (pinfunction "G_1") (pintype "passive"))
      (node (ref "R65") (pin "2") (pinfunction "2_2") (pintype "passive"))
      (node (ref "R68") (pin "1") (pinfunction "1_1") (pintype "passive"))
    )
    (net (code "52") (name "unconnected-(U15-NC-Pad5)") (class "Default")
      (node (ref "U15") (pin "5") (pinfunction "NC_5") (pintype "power_in+no_connect"))
    )
    (net (code "53") (name "unconnected-(U16-PA4-Pad12)") (class "Default")
      (node (ref "U16") (pin "12") (pinfunction "PA4_12") (pintype "bidirectional+no_connect"))
    )
    (net (code "54") (name "unconnected-(U16-PA6-Pad14)") (class "Default")
      (node (ref "U16") (pin "14") (pinfunction "PA6_14") (pintype "bidirectional+no_connect"))
    )
    (net (code "55") (name "unconnected-(U16-PA8-Pad30)") (class "Default")
      (node (ref "U16") (pin "30") (pinfunction "PA8_30") (pintype "bidirectional+no_connect"))
    )
    (net (code "56") (name "unconnected-(U16-PA9-Pad31)") (class "Default")
      (node (ref "U16") (pin "31") (pinfunction "PA9_31") (pintype "bidirectional+no_connect"))
    )
    (net (code "57") (name "unconnected-(U16-PA10-Pad32)") (class "Default")
      (node (ref "U16") (pin "32") (pinfunction "PA10_32") (pintype "bidirectional+no_connect"))
    )
    (net (code "58") (name "unconnected-(U16-PB3-Pad41)") (class "Default")
      (node (ref "U16") (pin "41") (pinfunction "PB3_41") (pintype "bidirectional+no_connect"))
    )
    (net (code "59") (name "unconnected-(U16-PB4-Pad42)") (class "Default")
      (node (ref "U16") (pin "42") (pinfunction "PB4_42") (pintype "bidirectional+no_connect"))
    )
    (net (code "60") (name "unconnected-(U16-PB5-Pad43)") (class "Default")
      (node (ref "U16") (pin "43") (pinfunction "PB5_43") (pintype "bidirectional+no_connect"))
    )
    (net (code "61") (name "unconnected-(U16-PB6-Pad44)") (class "Default")
      (node (ref "U16") (pin "44") (pinfunction "PB6_44") (pintype "bidirectional+no_connect"))
    )
    (net (code "62") (name "unconnected-(U16-PB7-Pad45)") (class "Default")
      (node (ref "U16") (pin "45") (pinfunction "PB7_45") (pintype "bidirectional+no_connect"))
    )
    (net (code "63") (name "unconnected-(U16-PB8-BOOT0-Pad46)") (class "Default")
      (node (ref "U16") (pin "46") (pinfunction "PB8-BOOT0_46") (pintype "bidirectional+no_connect"))
    )
    (net (code "64") (name "unconnected-(U16-PB9-Pad47)") (class "Default")
      (node (ref "U16") (pin "47") (pinfunction "PB9_47") (pintype "bidirectional+no_connect"))
    )
    (net (code "65") (name "unconnected-(U16-PB10-Pad22)") (class "Default")
      (node (ref "U16") (pin "22") (pinfunction "PB10_22") (pintype "bidirectional+no_connect"))
    )
    (net (code "66") (name "unconnected-(U16-PB13-Pad26)") (class "Default")
      (node (ref "U16") (pin "26") (pinfunction "PB13_26") (pintype "bidirectional+no_connect"))
    )
    (net (code "67") (name "unconnected-(U16-PC6-Pad29)") (class "Default")
      (node (ref "U16") (pin "29") (pinfunction "PC6_29") (pintype "bidirectional+no_connect"))
    )
    (net (code "68") (name "unconnected-(U16-PC10-Pad39)") (class "Default")
      (node (ref "U16") (pin "39") (pinfunction "PC10_39") (pintype "bidirectional+no_connect"))
    )
    (net (code "69") (name "unconnected-(U16-PC11-Pad40)") (class "Default")
      (node (ref "U16") (pin "40") (pinfunction "PC11_40") (pintype "bidirectional+no_connect"))
    )
    (net (code "70") (name "unconnected-(U16-PG10-NRST-Pad7)") (class "Default")
      (node (ref "U16") (pin "7") (pinfunction "PG10-NRST_7") (pintype "bidirectional+no_connect"))
    )
  )
)
